# RF_And_SD_Ticketing_Master.net
KiCad netlist of a schematic drawn in Altium Designer
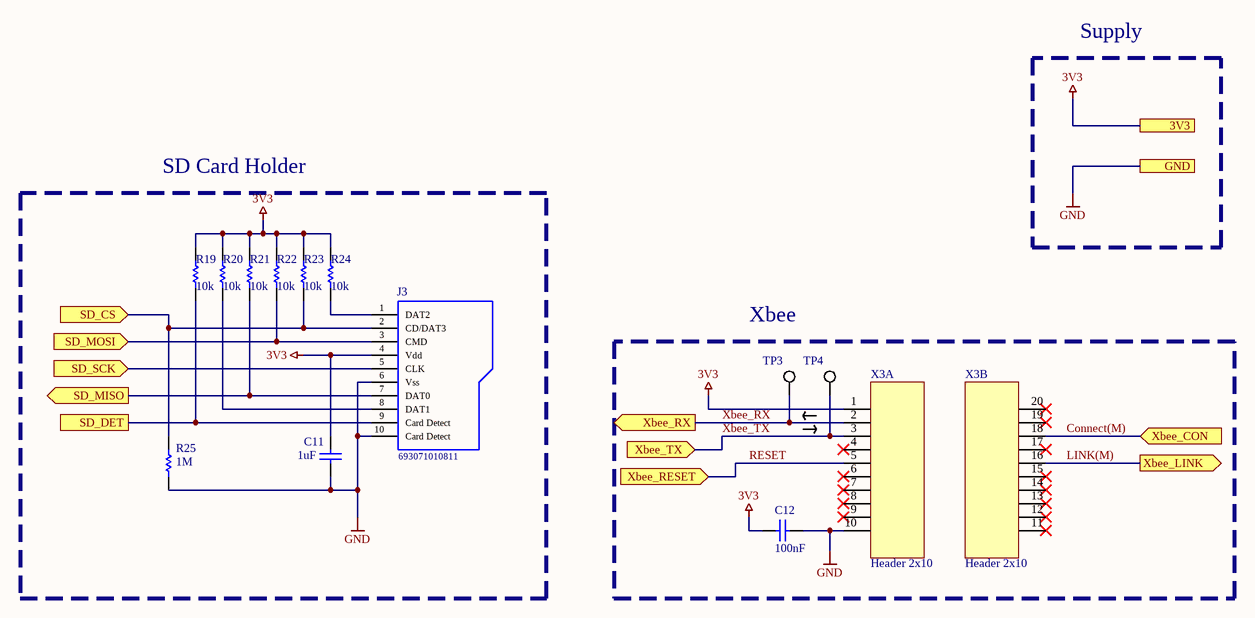
[diagram p0: RF_And_SD_Ticketing_Master.SchDoc]

(export (version "E")
  (design (tool "Eeschema 10.0.6"))
  (components
    (comp (ref "C11")
      (value "1uF")
      (footprint "6-0805_N")
      (description "Capacitor")
      (fields (field (name "PUBLISHER") "Altium Limited"))
      (libsource (lib "Miscellaneous Devices") (part "Cap"))
    )
    (comp (ref "C12")
      (value "100nF")
      (footprint "6-0805_N")
      (description "Capacitor")
      (libsource (lib "Miscellaneous Devices") (part "Cap"))
    )
    (comp (ref "J3")
      (value "693071010811")
      (footprint "693071010811")
      (description "WR-CRD Micro SD Card Connector, Push & Push, with card detection")
      (fields (field (name "PART NUMBER") "732-3819-1-ND") (field (name "PUBLISHER") "Wurth Elektronik"))
      (libsource (lib "ALTIUM-WR-CRD-rev18a") (part "693071010811"))
    )
    (comp (ref "R19")
      (value "10k")
      (footprint "RESC0805(2012)_L")
      (description "100K 0.125W 5% 0805 (2012 Metric)  SMD")
      (fields (field (name "TOLERANCE") "5 %") (field (name "POWER") "0.125 W"))
      (libsource (lib "Altium Content Vault") (part "CMP-1013-00122-1"))
    )
    (comp (ref "R20")
      (value "10k")
      (footprint "RESC0805(2012)_L")
      (description "100K 0.125W 5% 0805 (2012 Metric)  SMD")
      (fields (field (name "TOLERANCE") "5 %") (field (name "POWER") "0.125 W"))
      (libsource (lib "Altium Content Vault") (part "CMP-1013-00122-1"))
    )
    (comp (ref "R21")
      (value "10k")
      (footprint "RESC0805(2012)_L")
      (description "100K 0.125W 5% 0805 (2012 Metric)  SMD")
      (fields (field (name "TOLERANCE") "5 %") (field (name "POWER") "0.125 W"))
      (libsource (lib "Altium Content Vault") (part "CMP-1013-00122-1"))
    )
    (comp (ref "R22")
      (value "10k")
      (footprint "RESC0805(2012)_L")
      (description "100K 0.125W 5% 0805 (2012 Metric)  SMD")
      (fields (field (name "TOLERANCE") "5 %") (field (name "POWER") "0.125 W"))
      (libsource (lib "Altium Content Vault") (part "CMP-1013-00122-1"))
    )
    (comp (ref "R23")
      (value "10k")
      (footprint "RESC0805(2012)_L")
      (description "100K 0.125W 5% 0805 (2012 Metric)  SMD")
      (fields (field (name "TOLERANCE") "5 %") (field (name "POWER") "0.125 W"))
      (libsource (lib "Altium Content Vault") (part "CMP-1013-00122-1"))
    )
    (comp (ref "R24")
      (value "10k")
      (footprint "RESC0805(2012)_L")
      (description "100K 0.125W 5% 0805 (2012 Metric)  SMD")
      (fields (field (name "TOLERANCE") "5 %") (field (name "POWER") "0.125 W"))
      (libsource (lib "Altium Content Vault") (part "CMP-1013-00122-1"))
    )
    (comp (ref "R25")
      (value "1M")
      (footprint "RESC0805(2012)_L")
      (description "100K 0.125W 5% 0805 (2012 Metric)  SMD")
      (fields (field (name "TOLERANCE") "5 %") (field (name "POWER") "0.125 W"))
      (libsource (lib "Altium Content Vault") (part "CMP-1013-00122-1"))
    )
    (comp (ref "TP3")
      (value "~")
      (footprint "KSTN-5019_V")
      (description "Test Point, 1 Position SMD, RoHS, Tape and Reel")
      (libsource (lib "Altium Content Vault") (part "TESTPOINT_WHITE"))
    )
    (comp (ref "TP4")
      (value "~")
      (footprint "KSTN-5019_V")
      (description "Test Point, 1 Position SMD, RoHS, Tape and Reel")
      (libsource (lib "Altium Content Vault") (part "TESTPOINT_WHITE"))
    )
    (comp (ref "X3")
      (value "Header 2x10")
      (footprint "ZB-SB")
      (description "Header 2x10\r\nXbee de letml(1623) ou xbee XB24CAUIT-001")
      (libsource (lib "PCB_Ticketing_Master") (part "HDR ZB-SB 2x10_1"))
    )
  )
  (nets
    (net (code "1") (name "/Connect(M)") (class "Default") (node (ref "X3") (pin "18") (pintype "passive")))
    (net (code "2") (name "/LINK(M)") (class "Default") (node (ref "X3") (pin "16") (pintype "passive")))
    (net (code "3") (name "/RESET") (class "Default") (node (ref "X3") (pin "5") (pintype "passive")))
    (net (code "4") (name "/SD_CS") (class "Default")
      (node (ref "J3") (pin "2") (pinfunction "CD/DAT3_2") (pintype "passive"))
      (node (ref "R23") (pin "1") (pinfunction "1_1") (pintype "passive"))
      (node (ref "R25") (pin "2") (pinfunction "2_2") (pintype "passive"))
    )
    (net (code "5") (name "/SD_DET") (class "Default")
      (node (ref "J3") (pin "9") (pinfunction "Card_Detect_9") (pintype "passive"))
      (node (ref "R19") (pin "1") (pinfunction "1_1") (pintype "passive"))
    )
    (net (code "6") (name "/SD_MISO") (class "Default")
      (node (ref "J3") (pin "7") (pinfunction "DAT0_7") (pintype "passive"))
      (node (ref "R21") (pin "1") (pinfunction "1_1") (pintype "passive"))
    )
    (net (code "7") (name "/SD_MOSI") (class "Default")
      (node (ref "J3") (pin "3") (pinfunction "CMD_3") (pintype "passive"))
      (node (ref "R22") (pin "1") (pinfunction "1_1") (pintype "passive"))
    )
    (net (code "8") (name "/SD_SCK") (class "Default")
      (node (ref "J3") (pin "5") (pinfunction "CLK_5") (pintype "passive"))
    )
    (net (code "9") (name "/Xbee_RX") (class "Default")
      (node (ref "TP3") (pin "1") (pinfunction "1_1") (pintype "passive"))
      (node (ref "X3") (pin "2") (pintype "passive"))
    )
    (net (code "10") (name "/Xbee_TX") (class "Default")
      (node (ref "TP4") (pin "1") (pinfunction "1_1") (pintype "passive"))
      (node (ref "X3") (pin "3") (pintype "passive"))
    )
    (net (code "11") (name "3V3") (class "Default")
      (node (ref "C11") (pin "2") (pinfunction "2_2") (pintype "passive"))
      (node (ref "C12") (pin "2") (pinfunction "2_2") (pintype "passive"))
      (node (ref "J3") (pin "4") (pinfunction "Vdd_4") (pintype "passive"))
      (node (ref "R19") (pin "2") (pinfunction "2_2") (pintype "passive"))
      (node (ref "R20") (pin "2") (pinfunction "2_2") (pintype "passive"))
      (node (ref "R21") (pin "2") (pinfunction "2_2") (pintype "passive"))
      (node (ref "R22") (pin "2") (pinfunction "2_2") (pintype "passive"))
      (node (ref "R23") (pin "2") (pinfunction "2_2") (pintype "passive"))
      (node (ref "R24") (pin "2") (pinfunction "2_2") (pintype "passive"))
      (node (ref "X3") (pin "1") (pintype "passive"))
    )
    (net (code "12") (name "GND") (class "Default")
      (node (ref "C11") (pin "1") (pinfunction "1_1") (pintype "passive"))
      (node (ref "C12") (pin "1") (pinfunction "1_1") (pintype "passive"))
      (node (ref "J3") (pin "10") (pinfunction "Card_Detect_10") (pintype "passive"))
      (node (ref "J3") (pin "6") (pinfunction "Vss_6") (pintype "passive"))
      (node (ref "R25") (pin "1") (pinfunction "1_1") (pintype "passive"))
      (node (ref "X3") (pin "10") (pintype "passive"))
    )
    (net (code "13") (name "Net-(J3-DAT1)") (class "Default")
      (node (ref "J3") (pin "8") (pinfunction "DAT1_8") (pintype "passive"))
      (node (ref "R20") (pin "1") (pinfunction "1_1") (pintype "passive"))
    )
    (net (code "14") (name "Net-(J3-DAT2)") (class "Default")
      (node (ref "J3") (pin "1") (pinfunction "DAT2_1") (pintype "passive"))
      (node (ref "R24") (pin "1") (pinfunction "1_1") (pintype "passive"))
    )
    (net (code "15") (name "unconnected-(X3-Pad4)") (class "Default")
      (node (ref "X3") (pin "4") (pintype "passive+no_connect"))
    )
    (net (code "16") (name "unconnected-(X3-Pad6)") (class "Default")
      (node (ref "X3") (pin "6") (pintype "passive+no_connect"))
    )
    (net (code "17") (name "unconnected-(X3-Pad7)") (class "Default")
      (node (ref "X3") (pin "7") (pintype "passive+no_connect"))
    )
    (net (code "18") (name "unconnected-(X3-Pad8)") (class "Default")
      (node (ref "X3") (pin "8") (pintype "passive+no_connect"))
    )
    (net (code "19") (name "unconnected-(X3-Pad9)") (class "Default")
      (node (ref "X3") (pin "9") (pintype "passive+no_connect"))
    )
    (net (code "20") (name "unconnected-(X3-Pad11)") (class "Default")
      (node (ref "X3") (pin "11") (pintype "passive+no_connect"))
    )
    (net (code "21") (name "unconnected-(X3-Pad12)") (class "Default")
      (node (ref "X3") (pin "12") (pintype "passive+no_connect"))
    )
    (net (code "22") (name "unconnected-(X3-Pad13)") (class "Default")
      (node (ref "X3") (pin "13") (pintype "passive+no_connect"))
    )
    (net (code "23") (name "unconnected-(X3-Pad14)") (class "Default")
      (node (ref "X3") (pin "14") (pintype "passive+no_connect"))
    )
    (net (code "24") (name "unconnected-(X3-Pad15)") (class "Default")
      (node (ref "X3") (pin "15") (pintype "passive+no_connect"))
    )
    (net (code "25") (name "unconnected-(X3-Pad17)") (class "Default")
      (node (ref "X3") (pin "17") (pintype "passive+no_connect"))
    )
    (net (code "26") (name "unconnected-(X3-Pad19)") (class "Default")
      (node (ref "X3") (pin "19") (pintype "passive+no_connect"))
    )
    (net (code "27") (name "unconnected-(X3-Pad20)") (class "Default")
      (node (ref "X3") (pin "20") (pintype "passive+no_connect"))
    )
  )
)
